# SCH_NFC-Business-Card_2025-01-31.net
KiCad netlist of a schematic drawn in EasyEDA
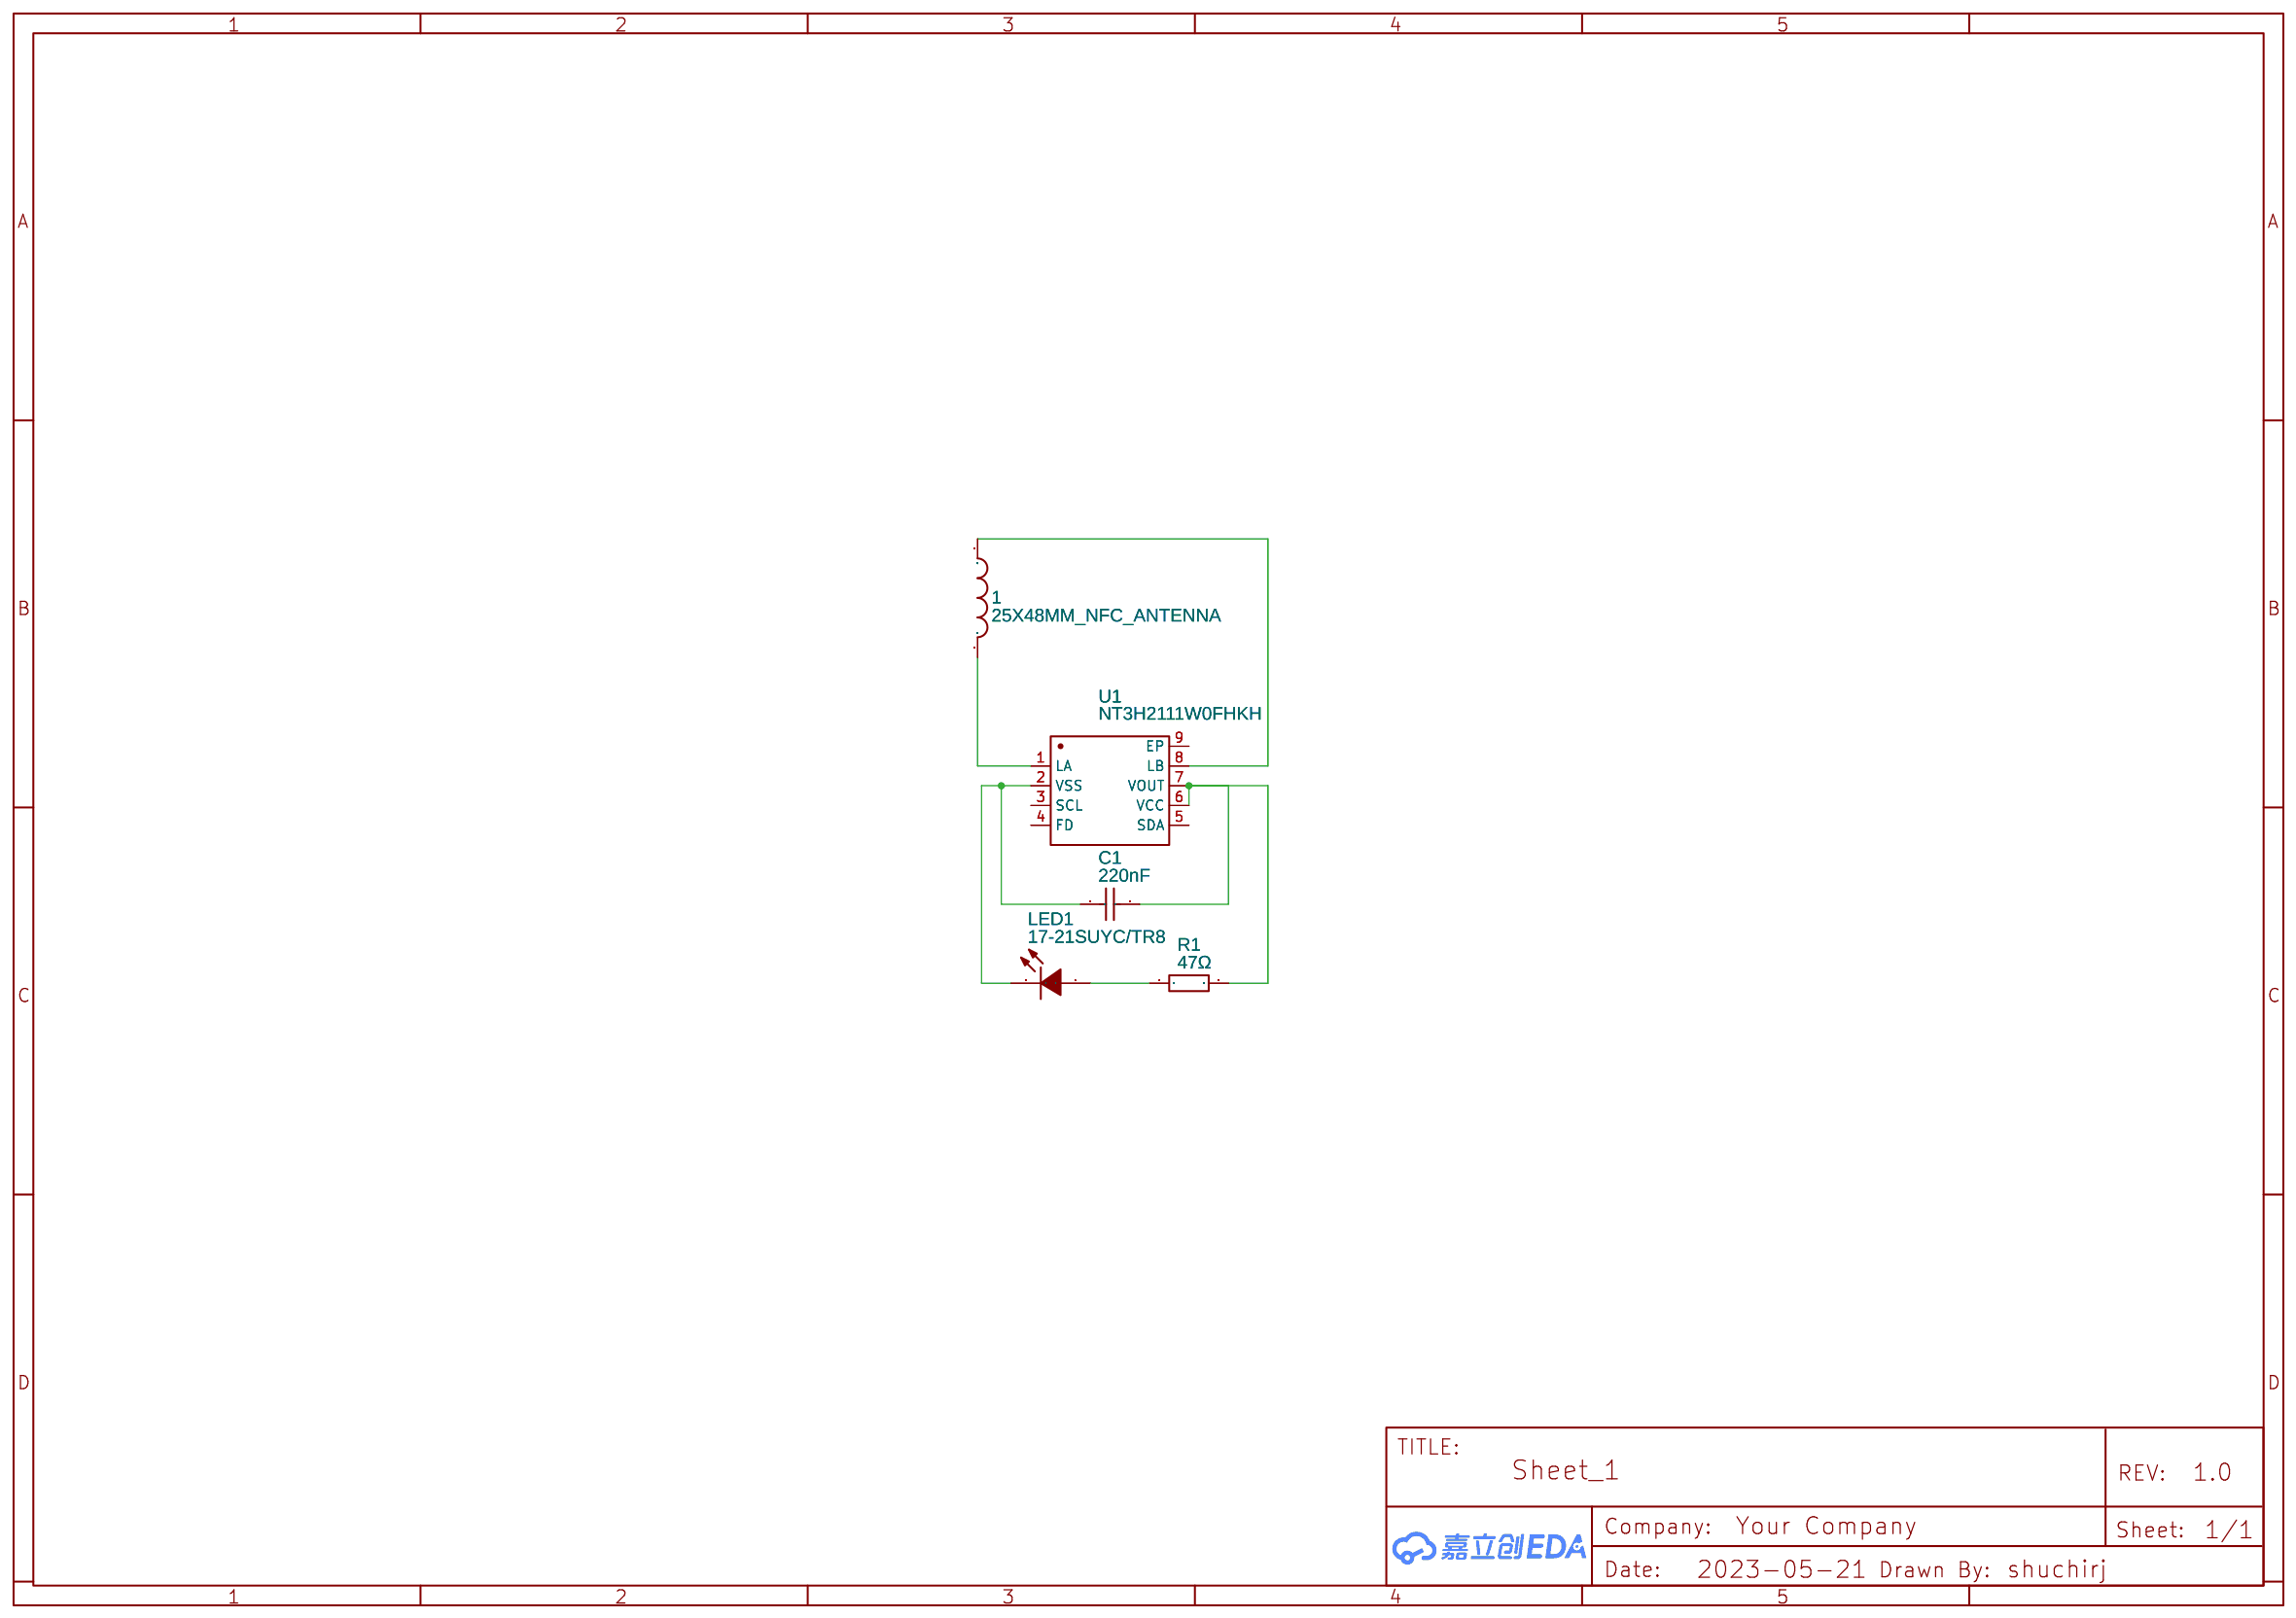
[diagram p0: schematic sheet]

(export (version "E")
  (design (tool "Eeschema 10.0.6"))
  (components
    (comp (ref "1") (value "25X48MM_NFC_ANTENNA") (libsource (lib "") (part "25X48MM_NFC_ANTENNA")))
    (comp (ref "C1")
      (value "220nF")
      (fields
        (field (name "Manufacturer Part") "CL10B224KA8NNNC")
        (field (name "Manufacturer") "SAMSUNG(三星)")
      )
      (libsource (lib "") (part "CL10B224KA8NNNC"))
    )
    (comp (ref "LED1")
      (value "17-21SUYC/TR8")
      (fields (field (name "Manufacturer Part") "KT-0805黄灯") (field (name "Manufacturer") "KENTO"))
      (libsource (lib "") (part "17-21SUYC/TR8"))
    )
    (comp (ref "R1")
      (value "47Ω")
      (fields
        (field (name "Manufacturer Part") "0603WAF470JT5E")
        (field (name "Manufacturer") "UNI-ROYAL(厚声)")
      )
      (libsource (lib "") (part "0603WAF470JT5E"))
    )
    (comp (ref "U1")
      (value "NT3H2111W0FHKH")
      (fields (field (name "Manufacturer") "NXP(恩智浦)"))
      (libsource (lib "") (part "NT3H2111W0FHKH"))
    )
  )
  (nets
    (net (code "1") (name "Net-(LED1-+)") (class "Default")
      (node (ref "LED1") (pin "1") (pinfunction "+_1") (pintype "unspecified"))
      (node (ref "R1") (pin "1") (pinfunction "1_1") (pintype "input"))
    )
    (net (code "2") (name "Net-(LED1--)") (class "Default")
      (node (ref "C1") (pin "1") (pinfunction "1_1") (pintype "input"))
      (node (ref "LED1") (pin "2") (pinfunction "-_2") (pintype "unspecified"))
      (node (ref "U1") (pin "2") (pinfunction "VSS_2") (pintype "unspecified"))
    )
    (net (code "3") (name "Net-(U1-LA)") (class "Default")
      (node (ref "1") (pin "P$2") (pinfunction "P$2_P$2") (pintype "bidirectional"))
      (node (ref "U1") (pin "1") (pinfunction "LA_1") (pintype "unspecified"))
    )
    (net (code "4") (name "Net-(U1-LB)") (class "Default")
      (node (ref "1") (pin "P$1") (pinfunction "P$1_P$1") (pintype "bidirectional"))
      (node (ref "U1") (pin "8") (pinfunction "LB_8") (pintype "unspecified"))
    )
    (net (code "5") (name "Net-(U1-VCC)") (class "Default")
      (node (ref "C1") (pin "2") (pinfunction "2_2") (pintype "input"))
      (node (ref "R1") (pin "2") (pinfunction "2_2") (pintype "input"))
      (node (ref "U1") (pin "6") (pinfunction "VCC_6") (pintype "unspecified"))
      (node (ref "U1") (pin "7") (pinfunction "VOUT_7") (pintype "unspecified"))
    )
    (net (code "6") (name "unconnected-(U1-EP-Pad9)") (class "Default")
      (node (ref "U1") (pin "9") (pinfunction "EP_9") (pintype "unspecified"))
    )
    (net (code "7") (name "unconnected-(U1-FD-Pad4)") (class "Default")
      (node (ref "U1") (pin "4") (pinfunction "FD_4") (pintype "unspecified"))
    )
    (net (code "8") (name "unconnected-(U1-SCL-Pad3)") (class "Default")
      (node (ref "U1") (pin "3") (pinfunction "SCL_3") (pintype "unspecified"))
    )
    (net (code "9") (name "unconnected-(U1-SDA-Pad5)") (class "Default")
      (node (ref "U1") (pin "5") (pinfunction "SDA_5") (pintype "unspecified"))
    )
  )
)
